# main.net
KiCad netlist of a schematic drawn in EAGLE
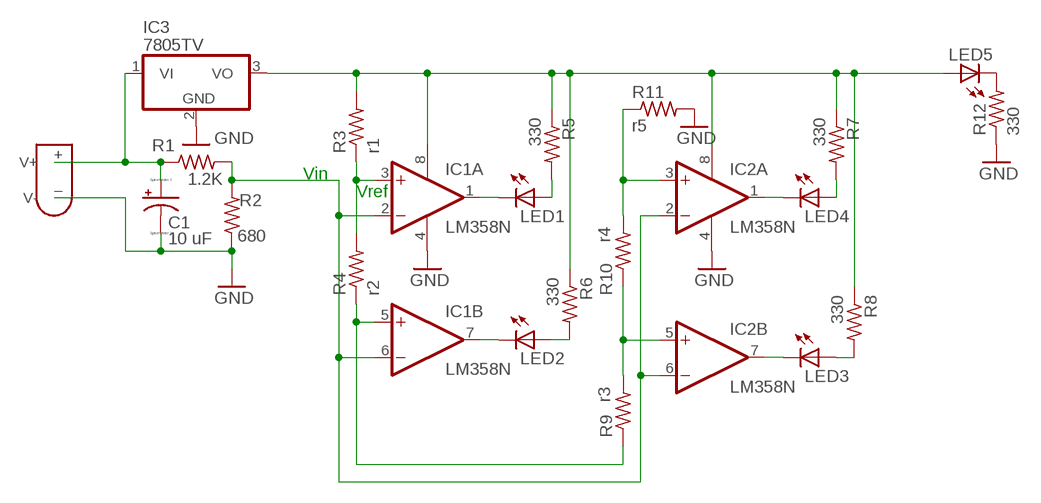
[diagram p0: schematic, sheet 1]

(export (version "E")
  (design (tool "Eeschema 10.0.6"))
  (components
    (comp (ref "C1")
      (value "10 uF")
      (footprint "eagle-import:E2-5")
      (libsource (lib "eagle-import") (part "CPOL-USE2-5"))
    )
    (comp (ref "IC1")
      (value "LM358N")
      (footprint "eagle-import:DIL08")
      (libsource (lib "eagle-import") (part "LM358N"))
    )
    (comp (ref "IC2")
      (value "LM358N")
      (footprint "eagle-import:DIL08")
      (libsource (lib "eagle-import") (part "LM358N"))
    )
    (comp (ref "IC3")
      (value "7805TV")
      (footprint "eagle-import:TO220V")
      (fields (field (name "SPICEPREFIX") "U"))
      (libsource (lib "eagle-import") (part "78TV05"))
    )
    (comp (ref "LED1")
      (value "LED5MM")
      (footprint "eagle-import:LED5MM")
      (libsource (lib "eagle-import") (part "LED5MM"))
    )
    (comp (ref "LED2")
      (value "LED5MM")
      (footprint "eagle-import:LED5MM")
      (libsource (lib "eagle-import") (part "LED5MM"))
    )
    (comp (ref "LED3")
      (value "LED5MM")
      (footprint "eagle-import:LED5MM")
      (libsource (lib "eagle-import") (part "LED5MM"))
    )
    (comp (ref "LED4")
      (value "LED5MM")
      (footprint "eagle-import:LED5MM")
      (libsource (lib "eagle-import") (part "LED5MM"))
    )
    (comp (ref "LED5")
      (value "LED5MM")
      (footprint "eagle-import:LED5MM")
      (libsource (lib "eagle-import") (part "LED5MM"))
    )
    (comp (ref "R1")
      (value "1.2K")
      (footprint "eagle-import:0207_7")
      (libsource (lib "eagle-import") (part "R-US_0207/7"))
    )
    (comp (ref "R2")
      (value "680")
      (footprint "eagle-import:0207_7")
      (libsource (lib "eagle-import") (part "R-US_0207/7"))
    )
    (comp (ref "R3")
      (value "r1")
      (footprint "eagle-import:0207_7")
      (libsource (lib "eagle-import") (part "R-US_0207/7"))
    )
    (comp (ref "R4")
      (value "r2")
      (footprint "eagle-import:0207_7")
      (libsource (lib "eagle-import") (part "R-US_0207/7"))
    )
    (comp (ref "R5")
      (value "330")
      (footprint "eagle-import:0207_7")
      (libsource (lib "eagle-import") (part "R-US_0207/7"))
    )
    (comp (ref "R6")
      (value "330")
      (footprint "eagle-import:0207_7")
      (libsource (lib "eagle-import") (part "R-US_0207/7"))
    )
    (comp (ref "R7")
      (value "330")
      (footprint "eagle-import:0207_7")
      (libsource (lib "eagle-import") (part "R-US_0207/7"))
    )
    (comp (ref "R8")
      (value "330")
      (footprint "eagle-import:0207_7")
      (libsource (lib "eagle-import") (part "R-US_0207/7"))
    )
    (comp (ref "R9")
      (value "r3")
      (footprint "eagle-import:0207_7")
      (libsource (lib "eagle-import") (part "R-US_0207/7"))
    )
    (comp (ref "R10")
      (value "r4")
      (footprint "eagle-import:0207_7")
      (libsource (lib "eagle-import") (part "R-US_0207/7"))
    )
    (comp (ref "R11")
      (value "r5")
      (footprint "eagle-import:0207_7")
      (libsource (lib "eagle-import") (part "R-US_0207/7"))
    )
    (comp (ref "R12")
      (value "330")
      (footprint "eagle-import:0207_7")
      (libsource (lib "eagle-import") (part "R-US_0207/7"))
    )
    (comp (ref "U$1")
      (value "XT30")
      (footprint "eagle-import:XT30")
      (libsource (lib "eagle-import") (part "XT30"))
    )
  )
  (nets
    (net (code "1") (name "GND") (class "Default")
      (node (ref "C1") (pin "-") (pinfunction "-_-") (pintype "passive"))
      (node (ref "IC1") (pin "4") (pinfunction "V-_4") (pintype "power_in"))
      (node (ref "IC2") (pin "4") (pinfunction "V-_4") (pintype "power_in"))
      (node (ref "IC3") (pin "2") (pinfunction "GND_2") (pintype "passive"))
      (node (ref "R11") (pin "2") (pinfunction "2_2") (pintype "passive"))
      (node (ref "R12") (pin "1") (pinfunction "1_1") (pintype "passive"))
      (node (ref "R2") (pin "1") (pinfunction "1_1") (pintype "passive"))
      (node (ref "U$1") (pin "–") (pinfunction "V-_–") (pintype "power_in"))
    )
    (net (code "2") (name "Net-(IC1A-+IN)") (class "Default")
      (node (ref "IC1") (pin "3") (pinfunction "+IN_3") (pintype "input"))
      (node (ref "R3") (pin "1") (pinfunction "1_1") (pintype "passive"))
      (node (ref "R4") (pin "2") (pinfunction "2_2") (pintype "passive"))
    )
    (net (code "3") (name "Net-(IC1A--IN)") (class "Default")
      (node (ref "IC1") (pin "2") (pinfunction "-IN_2") (pintype "input"))
      (node (ref "IC1") (pin "6") (pinfunction "-IN_6") (pintype "input"))
      (node (ref "IC2") (pin "2") (pinfunction "-IN_2") (pintype "input"))
      (node (ref "IC2") (pin "6") (pinfunction "-IN_6") (pintype "input"))
      (node (ref "R1") (pin "2") (pinfunction "2_2") (pintype "passive"))
      (node (ref "R2") (pin "2") (pinfunction "2_2") (pintype "passive"))
    )
    (net (code "4") (name "Net-(IC1A-OUT)") (class "Default")
      (node (ref "IC1") (pin "1") (pinfunction "OUT_1") (pintype "output"))
      (node (ref "LED1") (pin "K") (pinfunction "C_K") (pintype "passive"))
    )
    (net (code "5") (name "Net-(IC1B-+IN)") (class "Default")
      (node (ref "IC1") (pin "5") (pinfunction "+IN_5") (pintype "input"))
      (node (ref "R4") (pin "1") (pinfunction "1_1") (pintype "passive"))
      (node (ref "R9") (pin "1") (pinfunction "1_1") (pintype "passive"))
    )
    (net (code "6") (name "Net-(IC1B-OUT)") (class "Default")
      (node (ref "IC1") (pin "7") (pinfunction "OUT_7") (pintype "output"))
      (node (ref "LED2") (pin "K") (pinfunction "C_K") (pintype "passive"))
    )
    (net (code "7") (name "Net-(IC1C-V+)") (class "Default")
      (node (ref "IC1") (pin "8") (pinfunction "V+_8") (pintype "power_in"))
      (node (ref "IC2") (pin "8") (pinfunction "V+_8") (pintype "power_in"))
      (node (ref "IC3") (pin "3") (pinfunction "VO_3") (pintype "passive"))
      (node (ref "LED5") (pin "A") (pinfunction "A_A") (pintype "passive"))
      (node (ref "R3") (pin "2") (pinfunction "2_2") (pintype "passive"))
      (node (ref "R5") (pin "1") (pinfunction "1_1") (pintype "passive"))
      (node (ref "R6") (pin "1") (pinfunction "1_1") (pintype "passive"))
      (node (ref "R7") (pin "1") (pinfunction "1_1") (pintype "passive"))
      (node (ref "R8") (pin "1") (pinfunction "1_1") (pintype "passive"))
    )
    (net (code "8") (name "Net-(IC2A-+IN)") (class "Default")
      (node (ref "IC2") (pin "3") (pinfunction "+IN_3") (pintype "input"))
      (node (ref "R10") (pin "2") (pinfunction "2_2") (pintype "passive"))
      (node (ref "R11") (pin "1") (pinfunction "1_1") (pintype "passive"))
    )
    (net (code "9") (name "Net-(IC2A-OUT)") (class "Default")
      (node (ref "IC2") (pin "1") (pinfunction "OUT_1") (pintype "output"))
      (node (ref "LED4") (pin "K") (pinfunction "C_K") (pintype "passive"))
    )
    (net (code "10") (name "Net-(IC2B-+IN)") (class "Default")
      (node (ref "IC2") (pin "5") (pinfunction "+IN_5") (pintype "input"))
      (node (ref "R10") (pin "1") (pinfunction "1_1") (pintype "passive"))
      (node (ref "R9") (pin "2") (pinfunction "2_2") (pintype "passive"))
    )
    (net (code "11") (name "Net-(IC2B-OUT)") (class "Default")
      (node (ref "IC2") (pin "7") (pinfunction "OUT_7") (pintype "output"))
      (node (ref "LED3") (pin "K") (pinfunction "C_K") (pintype "passive"))
    )
    (net (code "12") (name "Net-(IC3-VI)") (class "Default")
      (node (ref "C1") (pin "+") (pinfunction "+_+") (pintype "passive"))
      (node (ref "IC3") (pin "1") (pinfunction "VI_1") (pintype "input"))
      (node (ref "R1") (pin "1") (pinfunction "1_1") (pintype "passive"))
      (node (ref "U$1") (pin "+") (pinfunction "V+_+") (pintype "power_in"))
    )
    (net (code "13") (name "Net-(LED1-PadA)") (class "Default")
      (node (ref "LED1") (pin "A") (pinfunction "A_A") (pintype "passive"))
      (node (ref "R5") (pin "2") (pinfunction "2_2") (pintype "passive"))
    )
    (net (code "14") (name "Net-(LED2-PadA)") (class "Default")
      (node (ref "LED2") (pin "A") (pinfunction "A_A") (pintype "passive"))
      (node (ref "R6") (pin "2") (pinfunction "2_2") (pintype "passive"))
    )
    (net (code "15") (name "Net-(LED3-PadA)") (class "Default")
      (node (ref "LED3") (pin "A") (pinfunction "A_A") (pintype "passive"))
      (node (ref "R8") (pin "2") (pinfunction "2_2") (pintype "passive"))
    )
    (net (code "16") (name "Net-(LED4-PadA)") (class "Default")
      (node (ref "LED4") (pin "A") (pinfunction "A_A") (pintype "passive"))
      (node (ref "R7") (pin "2") (pinfunction "2_2") (pintype "passive"))
    )
    (net (code "17") (name "Net-(LED5-C)") (class "Default")
      (node (ref "LED5") (pin "K") (pinfunction "C_K") (pintype "passive"))
      (node (ref "R12") (pin "2") (pinfunction "2_2") (pintype "passive"))
    )
  )
)
